# emojipad_v1.net
KiCad netlist of a schematic drawn in EAGLE
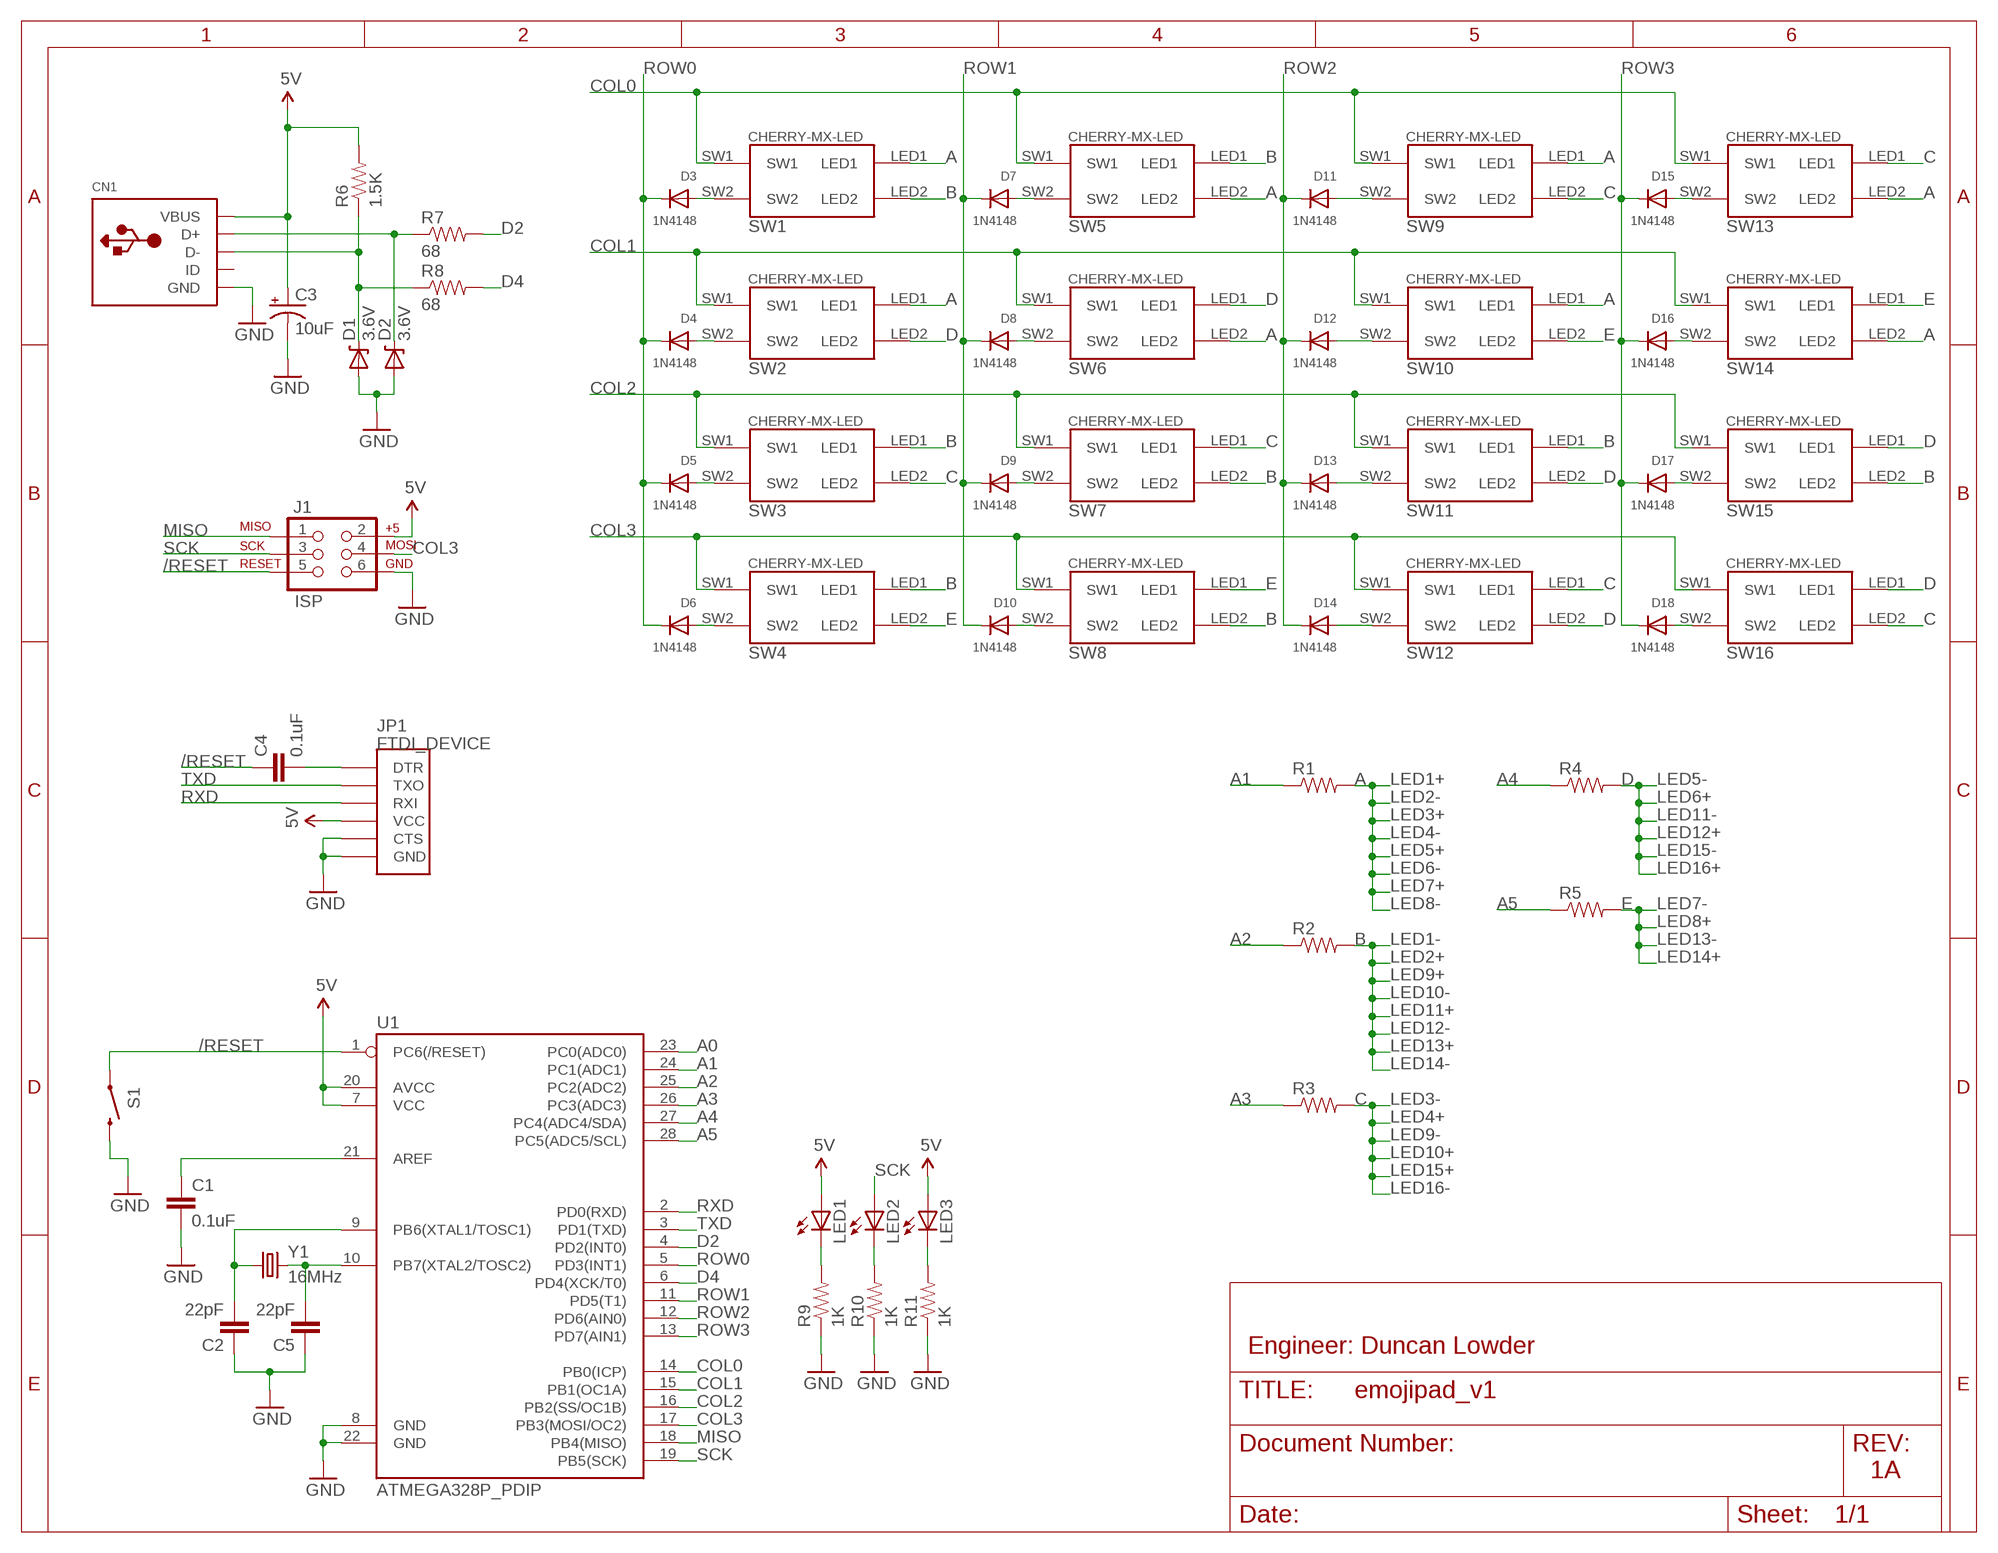
[diagram p0: schematic, sheet 1]

(export (version "E")
  (design (tool "Eeschema 10.0.6"))
  (components
    (comp (ref "C1")
      (value "0.1uF")
      (footprint "eagle-import:CAP-PTH-SMALL")
      (libsource (lib "eagle-import") (part "CAPPTH"))
    )
    (comp (ref "C2")
      (value "22pF")
      (footprint "eagle-import:CAP-PTH-SMALL")
      (libsource (lib "eagle-import") (part "CAPPTH"))
    )
    (comp (ref "C3")
      (value "10uF")
      (footprint "eagle-import:CPOL-RADIAL-10UF-25V")
      (libsource (lib "eagle-import") (part "CAP_POLPTH2"))
    )
    (comp (ref "C4")
      (value "0.1uF")
      (footprint "eagle-import:CAP-PTH-SMALL")
      (libsource (lib "eagle-import") (part "SparkFun-Passives_CAPPTH"))
    )
    (comp (ref "C5")
      (value "22pF")
      (footprint "eagle-import:CAP-PTH-SMALL")
      (libsource (lib "eagle-import") (part "CAPPTH"))
    )
    (comp (ref "CN1")
      (value "USBMOLEX")
      (footprint "eagle-import:USB-MINIB-THM-MOLEX")
      (libsource (lib "eagle-import") (part "USBMOLEX"))
    )
    (comp (ref "D1")
      (value "3.6V")
      (footprint "eagle-import:DIODE-ZENER")
      (libsource (lib "eagle-import") (part "DIODE-ZENERPTH"))
    )
    (comp (ref "D2")
      (value "3.6V")
      (footprint "eagle-import:DIODE-ZENER")
      (libsource (lib "eagle-import") (part "DIODE-ZENERPTH"))
    )
    (comp (ref "D3")
      (value "1N4148")
      (footprint "eagle-import:DO-1N4148")
      (libsource (lib "eagle-import") (part "DIODEDO-1N4148"))
    )
    (comp (ref "D4")
      (value "1N4148")
      (footprint "eagle-import:DO-1N4148")
      (libsource (lib "eagle-import") (part "DIODEDO-1N4148"))
    )
    (comp (ref "D5")
      (value "1N4148")
      (footprint "eagle-import:DO-1N4148")
      (libsource (lib "eagle-import") (part "DIODEDO-1N4148"))
    )
    (comp (ref "D6")
      (value "1N4148")
      (footprint "eagle-import:DO-1N4148")
      (libsource (lib "eagle-import") (part "DIODEDO-1N4148"))
    )
    (comp (ref "D7")
      (value "1N4148")
      (footprint "eagle-import:DO-1N4148")
      (libsource (lib "eagle-import") (part "DIODEDO-1N4148"))
    )
    (comp (ref "D8")
      (value "1N4148")
      (footprint "eagle-import:DO-1N4148")
      (libsource (lib "eagle-import") (part "DIODEDO-1N4148"))
    )
    (comp (ref "D9")
      (value "1N4148")
      (footprint "eagle-import:DO-1N4148")
      (libsource (lib "eagle-import") (part "DIODEDO-1N4148"))
    )
    (comp (ref "D10")
      (value "1N4148")
      (footprint "eagle-import:DO-1N4148")
      (libsource (lib "eagle-import") (part "DIODEDO-1N4148"))
    )
    (comp (ref "D11")
      (value "1N4148")
      (footprint "eagle-import:DO-1N4148")
      (libsource (lib "eagle-import") (part "DIODEDO-1N4148"))
    )
    (comp (ref "D12")
      (value "1N4148")
      (footprint "eagle-import:DO-1N4148")
      (libsource (lib "eagle-import") (part "DIODEDO-1N4148"))
    )
    (comp (ref "D13")
      (value "1N4148")
      (footprint "eagle-import:DO-1N4148")
      (libsource (lib "eagle-import") (part "DIODEDO-1N4148"))
    )
    (comp (ref "D14")
      (value "1N4148")
      (footprint "eagle-import:DO-1N4148")
      (libsource (lib "eagle-import") (part "DIODEDO-1N4148"))
    )
    (comp (ref "D15")
      (value "1N4148")
      (footprint "eagle-import:DO-1N4148")
      (libsource (lib "eagle-import") (part "DIODEDO-1N4148"))
    )
    (comp (ref "D16")
      (value "1N4148")
      (footprint "eagle-import:DO-1N4148")
      (libsource (lib "eagle-import") (part "DIODEDO-1N4148"))
    )
    (comp (ref "D17")
      (value "1N4148")
      (footprint "eagle-import:DO-1N4148")
      (libsource (lib "eagle-import") (part "DIODEDO-1N4148"))
    )
    (comp (ref "D18")
      (value "1N4148")
      (footprint "eagle-import:DO-1N4148")
      (libsource (lib "eagle-import") (part "DIODEDO-1N4148"))
    )
    (comp (ref "J1")
      (value "ISP")
      (footprint "eagle-import:2X3")
      (libsource (lib "eagle-import") (part "AVR_SPI_PRG_6PTH"))
    )
    (comp (ref "JP1")
      (value "FTDI_DEVICE")
      (footprint "eagle-import:FTDI_DEVICE_SIDE")
      (libsource (lib "eagle-import") (part "FTDI_DEVICE"))
    )
    (comp (ref "LED1")
      (value "LED3MM")
      (footprint "eagle-import:LED3MM")
      (libsource (lib "eagle-import") (part "LED3MM"))
    )
    (comp (ref "LED2")
      (value "LED3MM")
      (footprint "eagle-import:LED3MM")
      (libsource (lib "eagle-import") (part "LED3MM"))
    )
    (comp (ref "LED3")
      (value "LED3MM")
      (footprint "eagle-import:LED3MM")
      (libsource (lib "eagle-import") (part "LED3MM"))
    )
    (comp (ref "R1")
      (value "RESISTORAXIAL-0.3")
      (footprint "eagle-import:AXIAL-0.3")
      (libsource (lib "eagle-import") (part "RESISTORAXIAL-0.3"))
    )
    (comp (ref "R2")
      (value "RESISTORAXIAL-0.3")
      (footprint "eagle-import:AXIAL-0.3")
      (libsource (lib "eagle-import") (part "RESISTORAXIAL-0.3"))
    )
    (comp (ref "R3")
      (value "RESISTORAXIAL-0.3")
      (footprint "eagle-import:AXIAL-0.3")
      (libsource (lib "eagle-import") (part "RESISTORAXIAL-0.3"))
    )
    (comp (ref "R4")
      (value "RESISTORAXIAL-0.3")
      (footprint "eagle-import:AXIAL-0.3")
      (libsource (lib "eagle-import") (part "RESISTORAXIAL-0.3"))
    )
    (comp (ref "R5")
      (value "RESISTORAXIAL-0.3")
      (footprint "eagle-import:AXIAL-0.3")
      (libsource (lib "eagle-import") (part "RESISTORAXIAL-0.3"))
    )
    (comp (ref "R6")
      (value "1.5K")
      (footprint "eagle-import:AXIAL-0.3")
      (libsource (lib "eagle-import") (part "RESISTORAXIAL-0.3"))
    )
    (comp (ref "R7")
      (value "68")
      (footprint "eagle-import:AXIAL-0.3")
      (libsource (lib "eagle-import") (part "SparkFun-Resistors_RESISTORAXIAL-0.3"))
    )
    (comp (ref "R8")
      (value "68")
      (footprint "eagle-import:AXIAL-0.3")
      (libsource (lib "eagle-import") (part "SparkFun-Resistors_RESISTORAXIAL-0.3"))
    )
    (comp (ref "R9")
      (value "1K")
      (footprint "eagle-import:AXIAL-0.3")
      (libsource (lib "eagle-import") (part "RESISTORAXIAL-0.3"))
    )
    (comp (ref "R10")
      (value "1K")
      (footprint "eagle-import:AXIAL-0.3")
      (libsource (lib "eagle-import") (part "RESISTORAXIAL-0.3"))
    )
    (comp (ref "R11")
      (value "1K")
      (footprint "eagle-import:AXIAL-0.3")
      (libsource (lib "eagle-import") (part "RESISTORAXIAL-0.3"))
    )
    (comp (ref "S1")
      (value "SWITCH-MOMENTARY-2SIDE_EZ")
      (footprint "eagle-import:TACTILE-PTH-SIDEEZ")
      (libsource (lib "eagle-import") (part "SWITCH-MOMENTARY-2SIDE_EZ"))
    )
    (comp (ref "SW1")
      (value "CHERRY-MX-LED")
      (footprint "eagle-import:CHERRY-MX-LED")
      (libsource (lib "eagle-import") (part "CHERRY-MX-LED"))
    )
    (comp (ref "SW2")
      (value "CHERRY-MX-LED")
      (footprint "eagle-import:CHERRY-MX-LED")
      (libsource (lib "eagle-import") (part "CHERRY-MX-LED"))
    )
    (comp (ref "SW3")
      (value "CHERRY-MX-LED")
      (footprint "eagle-import:CHERRY-MX-LED")
      (libsource (lib "eagle-import") (part "CHERRY-MX-LED"))
    )
    (comp (ref "SW4")
      (value "CHERRY-MX-LED")
      (footprint "eagle-import:CHERRY-MX-LED")
      (libsource (lib "eagle-import") (part "CHERRY-MX-LED"))
    )
    (comp (ref "SW5")
      (value "CHERRY-MX-LED")
      (footprint "eagle-import:CHERRY-MX-LED")
      (libsource (lib "eagle-import") (part "CHERRY-MX-LED"))
    )
    (comp (ref "SW6")
      (value "CHERRY-MX-LED")
      (footprint "eagle-import:CHERRY-MX-LED")
      (libsource (lib "eagle-import") (part "CHERRY-MX-LED"))
    )
    (comp (ref "SW7")
      (value "CHERRY-MX-LED")
      (footprint "eagle-import:CHERRY-MX-LED")
      (libsource (lib "eagle-import") (part "CHERRY-MX-LED"))
    )
    (comp (ref "SW8")
      (value "CHERRY-MX-LED")
      (footprint "eagle-import:CHERRY-MX-LED")
      (libsource (lib "eagle-import") (part "CHERRY-MX-LED"))
    )
    (comp (ref "SW9")
      (value "CHERRY-MX-LED")
      (footprint "eagle-import:CHERRY-MX-LED")
      (libsource (lib "eagle-import") (part "CHERRY-MX-LED"))
    )
    (comp (ref "SW10")
      (value "CHERRY-MX-LED")
      (footprint "eagle-import:CHERRY-MX-LED")
      (libsource (lib "eagle-import") (part "CHERRY-MX-LED"))
    )
    (comp (ref "SW11")
      (value "CHERRY-MX-LED")
      (footprint "eagle-import:CHERRY-MX-LED")
      (libsource (lib "eagle-import") (part "CHERRY-MX-LED"))
    )
    (comp (ref "SW12")
      (value "CHERRY-MX-LED")
      (footprint "eagle-import:CHERRY-MX-LED")
      (libsource (lib "eagle-import") (part "CHERRY-MX-LED"))
    )
    (comp (ref "SW13")
      (value "CHERRY-MX-LED")
      (footprint "eagle-import:CHERRY-MX-LED")
      (libsource (lib "eagle-import") (part "CHERRY-MX-LED"))
    )
    (comp (ref "SW14")
      (value "CHERRY-MX-LED")
      (footprint "eagle-import:CHERRY-MX-LED")
      (libsource (lib "eagle-import") (part "CHERRY-MX-LED"))
    )
    (comp (ref "SW15")
      (value "CHERRY-MX-LED")
      (footprint "eagle-import:CHERRY-MX-LED")
      (libsource (lib "eagle-import") (part "CHERRY-MX-LED"))
    )
    (comp (ref "SW16")
      (value "CHERRY-MX-LED")
      (footprint "eagle-import:CHERRY-MX-LED")
      (libsource (lib "eagle-import") (part "CHERRY-MX-LED"))
    )
    (comp (ref "U1")
      (value "ATMEGA328P_PDIP")
      (footprint "eagle-import:DIL28-3")
      (libsource (lib "eagle-import") (part "ATMEGA328P_PDIP"))
    )
    (comp (ref "Y1")
      (value "16MHz")
      (footprint "eagle-import:HC49US")
      (libsource (lib "eagle-import") (part "CRYSTALHC49US"))
    )
  )
  (nets
    (net (code "1") (name "/A") (class "Default")
      (node (ref "R1") (pin "P$2") (pinfunction "2_P$2") (pintype "passive"))
      (node (ref "SW1") (pin "LED1") (pinfunction "LED1_LED1") (pintype "bidirectional"))
      (node (ref "SW10") (pin "LED1") (pinfunction "LED1_LED1") (pintype "bidirectional"))
      (node (ref "SW13") (pin "LED2") (pinfunction "LED2_LED2") (pintype "bidirectional"))
      (node (ref "SW14") (pin "LED2") (pinfunction "LED2_LED2") (pintype "bidirectional"))
      (node (ref "SW2") (pin "LED1") (pinfunction "LED1_LED1") (pintype "bidirectional"))
      (node (ref "SW5") (pin "LED2") (pinfunction "LED2_LED2") (pintype "bidirectional"))
      (node (ref "SW6") (pin "LED2") (pinfunction "LED2_LED2") (pintype "bidirectional"))
      (node (ref "SW9") (pin "LED1") (pinfunction "LED1_LED1") (pintype "bidirectional"))
    )
    (net (code "2") (name "/A0") (class "Default")
      (node (ref "U1") (pin "23") (pinfunction "PC0(ADC0)_23") (pintype "bidirectional"))
    )
    (net (code "3") (name "/A1") (class "Default")
      (node (ref "R1") (pin "P$1") (pinfunction "1_P$1") (pintype "passive"))
      (node (ref "U1") (pin "24") (pinfunction "PC1(ADC1)_24") (pintype "bidirectional"))
    )
    (net (code "4") (name "/A2") (class "Default")
      (node (ref "R2") (pin "P$1") (pinfunction "1_P$1") (pintype "passive"))
      (node (ref "U1") (pin "25") (pinfunction "PC2(ADC2)_25") (pintype "bidirectional"))
    )
    (net (code "5") (name "/A3") (class "Default")
      (node (ref "R3") (pin "P$1") (pinfunction "1_P$1") (pintype "passive"))
      (node (ref "U1") (pin "26") (pinfunction "PC3(ADC3)_26") (pintype "bidirectional"))
    )
    (net (code "6") (name "/A4") (class "Default")
      (node (ref "R4") (pin "P$1") (pinfunction "1_P$1") (pintype "passive"))
      (node (ref "U1") (pin "27") (pinfunction "PC4(ADC4/SDA)_27") (pintype "bidirectional"))
    )
    (net (code "7") (name "/A5") (class "Default")
      (node (ref "R5") (pin "P$1") (pinfunction "1_P$1") (pintype "passive"))
      (node (ref "U1") (pin "28") (pinfunction "PC5(ADC5/SCL)_28") (pintype "bidirectional"))
    )
    (net (code "8") (name "/B") (class "Default")
      (node (ref "R2") (pin "P$2") (pinfunction "2_P$2") (pintype "passive"))
      (node (ref "SW1") (pin "LED2") (pinfunction "LED2_LED2") (pintype "bidirectional"))
      (node (ref "SW11") (pin "LED1") (pinfunction "LED1_LED1") (pintype "bidirectional"))
      (node (ref "SW15") (pin "LED2") (pinfunction "LED2_LED2") (pintype "bidirectional"))
      (node (ref "SW3") (pin "LED1") (pinfunction "LED1_LED1") (pintype "bidirectional"))
      (node (ref "SW4") (pin "LED1") (pinfunction "LED1_LED1") (pintype "bidirectional"))
      (node (ref "SW5") (pin "LED1") (pinfunction "LED1_LED1") (pintype "bidirectional"))
      (node (ref "SW7") (pin "LED2") (pinfunction "LED2_LED2") (pintype "bidirectional"))
      (node (ref "SW8") (pin "LED2") (pinfunction "LED2_LED2") (pintype "bidirectional"))
    )
    (net (code "9") (name "/C") (class "Default")
      (node (ref "R3") (pin "P$2") (pinfunction "2_P$2") (pintype "passive"))
      (node (ref "SW12") (pin "LED1") (pinfunction "LED1_LED1") (pintype "bidirectional"))
      (node (ref "SW13") (pin "LED1") (pinfunction "LED1_LED1") (pintype "bidirectional"))
      (node (ref "SW16") (pin "LED2") (pinfunction "LED2_LED2") (pintype "bidirectional"))
      (node (ref "SW3") (pin "LED2") (pinfunction "LED2_LED2") (pintype "bidirectional"))
      (node (ref "SW7") (pin "LED1") (pinfunction "LED1_LED1") (pintype "bidirectional"))
      (node (ref "SW9") (pin "LED2") (pinfunction "LED2_LED2") (pintype "bidirectional"))
    )
    (net (code "10") (name "/COL0") (class "Default")
      (node (ref "SW1") (pin "SW1") (pinfunction "SW1_SW1") (pintype "bidirectional"))
      (node (ref "SW13") (pin "SW1") (pinfunction "SW1_SW1") (pintype "bidirectional"))
      (node (ref "SW5") (pin "SW1") (pinfunction "SW1_SW1") (pintype "bidirectional"))
      (node (ref "SW9") (pin "SW1") (pinfunction "SW1_SW1") (pintype "bidirectional"))
      (node (ref "U1") (pin "14") (pinfunction "PB0(ICP)_14") (pintype "bidirectional"))
    )
    (net (code "11") (name "/COL1") (class "Default")
      (node (ref "SW10") (pin "SW1") (pinfunction "SW1_SW1") (pintype "bidirectional"))
      (node (ref "SW14") (pin "SW1") (pinfunction "SW1_SW1") (pintype "bidirectional"))
      (node (ref "SW2") (pin "SW1") (pinfunction "SW1_SW1") (pintype "bidirectional"))
      (node (ref "SW6") (pin "SW1") (pinfunction "SW1_SW1") (pintype "bidirectional"))
      (node (ref "U1") (pin "15") (pinfunction "PB1(OC1A)_15") (pintype "bidirectional"))
    )
    (net (code "12") (name "/COL2") (class "Default")
      (node (ref "SW11") (pin "SW1") (pinfunction "SW1_SW1") (pintype "bidirectional"))
      (node (ref "SW15") (pin "SW1") (pinfunction "SW1_SW1") (pintype "bidirectional"))
      (node (ref "SW3") (pin "SW1") (pinfunction "SW1_SW1") (pintype "bidirectional"))
      (node (ref "SW7") (pin "SW1") (pinfunction "SW1_SW1") (pintype "bidirectional"))
      (node (ref "U1") (pin "16") (pinfunction "PB2(SS/OC1B)_16") (pintype "bidirectional"))
    )
    (net (code "13") (name "/COL3") (class "Default")
      (node (ref "J1") (pin "4") (pinfunction "4_4") (pintype "passive"))
      (node (ref "SW12") (pin "SW1") (pinfunction "SW1_SW1") (pintype "bidirectional"))
      (node (ref "SW16") (pin "SW1") (pinfunction "SW1_SW1") (pintype "bidirectional"))
      (node (ref "SW4") (pin "SW1") (pinfunction "SW1_SW1") (pintype "bidirectional"))
      (node (ref "SW8") (pin "SW1") (pinfunction "SW1_SW1") (pintype "bidirectional"))
      (node (ref "U1") (pin "17") (pinfunction "PB3(MOSI/OC2)_17") (pintype "bidirectional"))
    )
    (net (code "14") (name "/D") (class "Default")
      (node (ref "R4") (pin "P$2") (pinfunction "2_P$2") (pintype "passive"))
      (node (ref "SW11") (pin "LED2") (pinfunction "LED2_LED2") (pintype "bidirectional"))
      (node (ref "SW12") (pin "LED2") (pinfunction "LED2_LED2") (pintype "bidirectional"))
      (node (ref "SW15") (pin "LED1") (pinfunction "LED1_LED1") (pintype "bidirectional"))
      (node (ref "SW16") (pin "LED1") (pinfunction "LED1_LED1") (pintype "bidirectional"))
      (node (ref "SW2") (pin "LED2") (pinfunction "LED2_LED2") (pintype "bidirectional"))
      (node (ref "SW6") (pin "LED1") (pinfunction "LED1_LED1") (pintype "bidirectional"))
    )
    (net (code "15") (name "/D2") (class "Default")
      (node (ref "R7") (pin "P$2") (pinfunction "2_P$2") (pintype "passive"))
      (node (ref "U1") (pin "4") (pinfunction "PD2(INT0)_4") (pintype "bidirectional"))
    )
    (net (code "16") (name "/D4") (class "Default")
      (node (ref "R8") (pin "P$2") (pinfunction "2_P$2") (pintype "passive"))
      (node (ref "U1") (pin "6") (pinfunction "PD4(XCK/T0)_6") (pintype "bidirectional"))
    )
    (net (code "17") (name "/E") (class "Default")
      (node (ref "R5") (pin "P$2") (pinfunction "2_P$2") (pintype "passive"))
      (node (ref "SW10") (pin "LED2") (pinfunction "LED2_LED2") (pintype "bidirectional"))
      (node (ref "SW14") (pin "LED1") (pinfunction "LED1_LED1") (pintype "bidirectional"))
      (node (ref "SW4") (pin "LED2") (pinfunction "LED2_LED2") (pintype "bidirectional"))
      (node (ref "SW8") (pin "LED1") (pinfunction "LED1_LED1") (pintype "bidirectional"))
    )
    (net (code "18") (name "/MISO") (class "Default")
      (node (ref "J1") (pin "1") (pinfunction "1_1") (pintype "passive"))
      (node (ref "U1") (pin "18") (pinfunction "PB4(MISO)_18") (pintype "bidirectional"))
    )
    (net (code "19") (name "/ROW0") (class "Default")
      (node (ref "D3") (pin "C") (pinfunction "C_C") (pintype "passive"))
      (node (ref "D4") (pin "C") (pinfunction "C_C") (pintype "passive"))
      (node (ref "D5") (pin "C") (pinfunction "C_C") (pintype "passive"))
      (node (ref "D6") (pin "C") (pinfunction "C_C") (pintype "passive"))
      (node (ref "U1") (pin "5") (pinfunction "PD3(INT1)_5") (pintype "bidirectional"))
    )
    (net (code "20") (name "/ROW1") (class "Default")
      (node (ref "D10") (pin "C") (pinfunction "C_C") (pintype "passive"))
      (node (ref "D7") (pin "C") (pinfunction "C_C") (pintype "passive"))
      (node (ref "D8") (pin "C") (pinfunction "C_C") (pintype "passive"))
      (node (ref "D9") (pin "C") (pinfunction "C_C") (pintype "passive"))
      (node (ref "U1") (pin "11") (pinfunction "PD5(T1)_11") (pintype "bidirectional"))
    )
    (net (code "21") (name "/ROW2") (class "Default")
      (node (ref "D11") (pin "C") (pinfunction "C_C") (pintype "passive"))
      (node (ref "D12") (pin "C") (pinfunction "C_C") (pintype "passive"))
      (node (ref "D13") (pin "C") (pinfunction "C_C") (pintype "passive"))
      (node (ref "D14") (pin "C") (pinfunction "C_C") (pintype "passive"))
      (node (ref "U1") (pin "12") (pinfunction "PD6(AIN0)_12") (pintype "bidirectional"))
    )
    (net (code "22") (name "/ROW3") (class "Default")
      (node (ref "D15") (pin "C") (pinfunction "C_C") (pintype "passive"))
      (node (ref "D16") (pin "C") (pinfunction "C_C") (pintype "passive"))
      (node (ref "D17") (pin "C") (pinfunction "C_C") (pintype "passive"))
      (node (ref "D18") (pin "C") (pinfunction "C_C") (pintype "passive"))
      (node (ref "U1") (pin "13") (pinfunction "PD7(AIN1)_13") (pintype "bidirectional"))
    )
    (net (code "23") (name "/RXD") (class "Default")
      (node (ref "JP1") (pin "P$3") (pinfunction "RXI_P$3") (pintype "bidirectional"))
      (node (ref "U1") (pin "2") (pinfunction "PD0(RXD)_2") (pintype "bidirectional"))
    )
    (net (code "24") (name "/SCK") (class "Default")
      (node (ref "J1") (pin "3") (pinfunction "3_3") (pintype "passive"))
      (node (ref "LED2") (pin "A") (pinfunction "A_A") (pintype "passive"))
      (node (ref "U1") (pin "19") (pinfunction "PB5(SCK)_19") (pintype "bidirectional"))
    )
    (net (code "25") (name "/TXD") (class "Default")
      (node (ref "JP1") (pin "P$2") (pinfunction "TXO_P$2") (pintype "bidirectional"))
      (node (ref "U1") (pin "3") (pinfunction "PD1(TXD)_3") (pintype "bidirectional"))
    )
    (net (code "26") (name "/{slash}RESET") (class "Default")
      (node (ref "C4") (pin "1") (pinfunction "1_1") (pintype "passive"))
      (node (ref "J1") (pin "5") (pinfunction "5_5") (pintype "passive"))
      (node (ref "S1") (pin "1") (pinfunction "1_1") (pintype "passive"))
      (node (ref "U1") (pin "1") (pinfunction "PC6(/RESET)_1") (pintype "bidirectional"))
    )
    (net (code "27") (name "5V") (class "Default")
      (node (ref "C3") (pin "1") (pinfunction "+_1") (pintype "passive"))
      (node (ref "CN1") (pin "VBUS") (pinfunction "VBUS_VBUS") (pintype "power_in"))
      (node (ref "J1") (pin "2") (pinfunction "2_2") (pintype "passive"))
      (node (ref "JP1") (pin "P$4") (pinfunction "VCC_P$4") (pintype "bidirectional"))
      (node (ref "LED1") (pin "A") (pinfunction "A_A") (pintype "passive"))
      (node (ref "LED3") (pin "A") (pinfunction "A_A") (pintype "passive"))
      (node (ref "R6") (pin "P$2") (pinfunction "2_P$2") (pintype "passive"))
      (node (ref "U1") (pin "20") (pinfunction "AVCC_20") (pintype "bidirectional"))
      (node (ref "U1") (pin "7") (pinfunction "VCC_7") (pintype "bidirectional"))
    )
    (net (code "28") (name "GND") (class "Default")
      (node (ref "C1") (pin "2") (pinfunction "2_2") (pintype "passive"))
      (node (ref "C2") (pin "1") (pinfunction "1_1") (pintype "passive"))
      (node (ref "C3") (pin "2") (pinfunction "-_2") (pintype "passive"))
      (node (ref "C5") (pin "1") (pinfunction "1_1") (pintype "passive"))
      (node (ref "CN1") (pin "GND") (pinfunction "GND_GND") (pintype "power_in"))
      (node (ref "D1") (pin "P$2") (pinfunction "A_P$2") (pintype "passive"))
      (node (ref "D2") (pin "P$2") (pinfunction "A_P$2") (pintype "passive"))
      (node (ref "J1") (pin "6") (pinfunction "6_6") (pintype "passive"))
      (node (ref "JP1") (pin "P$5") (pinfunction "CTS_P$5") (pintype "bidirectional"))
      (node (ref "JP1") (pin "P$6") (pinfunction "GND_P$6") (pintype "bidirectional"))
      (node (ref "R10") (pin "P$1") (pinfunction "1_P$1") (pintype "passive"))
      (node (ref "R11") (pin "P$1") (pinfunction "1_P$1") (pintype "passive"))
      (node (ref "R9") (pin "P$1") (pinfunction "1_P$1") (pintype "passive"))
      (node (ref "S1") (pin "2") (pinfunction "2_2") (pintype "passive"))
      (node (ref "U1") (pin "22") (pinfunction "GND_22") (pintype "bidirectional"))
      (node (ref "U1") (pin "8") (pinfunction "GND_8") (pintype "bidirectional"))
    )
    (net (code "29") (name "Net-(D1-C)") (class "Default")
      (node (ref "CN1") (pin "D-") (pinfunction "D-_D-") (pintype "bidirectional"))
      (node (ref "D1") (pin "P$1") (pinfunction "C_P$1") (pintype "passive"))
      (node (ref "R6") (pin "P$1") (pinfunction "1_P$1") (pintype "passive"))
      (node (ref "R8") (pin "P$1") (pinfunction "1_P$1") (pintype "passive"))
    )
    (net (code "30") (name "Net-(D2-C)") (class "Default")
      (node (ref "CN1") (pin "D+") (pinfunction "D+_D+") (pintype "bidirectional"))
      (node (ref "D2") (pin "P$1") (pinfunction "C_P$1") (pintype "passive"))
      (node (ref "R7") (pin "P$1") (pinfunction "1_P$1") (pintype "passive"))
    )
    (net (code "31") (name "Net-(D3-PadA)") (class "Default")
      (node (ref "D3") (pin "A") (pinfunction "A_A") (pintype "passive"))
      (node (ref "SW1") (pin "SW2") (pinfunction "SW2_SW2") (pintype "bidirectional"))
    )
    (net (code "32") (name "Net-(D4-PadA)") (class "Default")
      (node (ref "D4") (pin "A") (pinfunction "A_A") (pintype "passive"))
      (node (ref "SW2") (pin "SW2") (pinfunction "SW2_SW2") (pintype "bidirectional"))
    )
    (net (code "33") (name "Net-(D5-PadA)") (class "Default")
      (node (ref "D5") (pin "A") (pinfunction "A_A") (pintype "passive"))
      (node (ref "SW3") (pin "SW2") (pinfunction "SW2_SW2") (pintype "bidirectional"))
    )
    (net (code "34") (name "Net-(D6-PadA)") (class "Default")
      (node (ref "D6") (pin "A") (pinfunction "A_A") (pintype "passive"))
      (node (ref "SW4") (pin "SW2") (pinfunction "SW2_SW2") (pintype "bidirectional"))
    )
    (net (code "35") (name "Net-(D7-PadA)") (class "Default")
      (node (ref "D7") (pin "A") (pinfunction "A_A") (pintype "passive"))
      (node (ref "SW5") (pin "SW2") (pinfunction "SW2_SW2") (pintype "bidirectional"))
    )
    (net (code "36") (name "Net-(D8-PadA)") (class "Default")
      (node (ref "D8") (pin "A") (pinfunction "A_A") (pintype "passive"))
      (node (ref "SW6") (pin "SW2") (pinfunction "SW2_SW2") (pintype "bidirectional"))
    )
    (net (code "37") (name "Net-(D9-PadA)") (class "Default")
      (node (ref "D9") (pin "A") (pinfunction "A_A") (pintype "passive"))
      (node (ref "SW7") (pin "SW2") (pinfunction "SW2_SW2") (pintype "bidirectional"))
    )
    (net (code "38") (name "Net-(D10-PadA)") (class "Default")
      (node (ref "D10") (pin "A") (pinfunction "A_A") (pintype "passive"))
      (node (ref "SW8") (pin "SW2") (pinfunction "SW2_SW2") (pintype "bidirectional"))
    )
    (net (code "39") (name "Net-(D11-PadA)") (class "Default")
      (node (ref "D11") (pin "A") (pinfunction "A_A") (pintype "passive"))
      (node (ref "SW9") (pin "SW2") (pinfunction "SW2_SW2") (pintype "bidirectional"))
    )
    (net (code "40") (name "Net-(D12-PadA)") (class "Default")
      (node (ref "D12") (pin "A") (pinfunction "A_A") (pintype "passive"))
      (node (ref "SW10") (pin "SW2") (pinfunction "SW2_SW2") (pintype "bidirectional"))
    )
    (net (code "41") (name "Net-(D13-PadA)") (class "Default")
      (node (ref "D13") (pin "A") (pinfunction "A_A") (pintype "passive"))
      (node (ref "SW11") (pin "SW2") (pinfunction "SW2_SW2") (pintype "bidirectional"))
    )
    (net (code "42") (name "Net-(D14-PadA)") (class "Default")
      (node (ref "D14") (pin "A") (pinfunction "A_A") (pintype "passive"))
      (node (ref "SW12") (pin "SW2") (pinfunction "SW2_SW2") (pintype "bidirectional"))
    )
    (net (code "43") (name "Net-(D15-PadA)") (class "Default")
      (node (ref "D15") (pin "A") (pinfunction "A_A") (pintype "passive"))
      (node (ref "SW13") (pin "SW2") (pinfunction "SW2_SW2") (pintype "bidirectional"))
    )
    (net (code "44") (name "Net-(D16-PadA)") (class "Default")
      (node (ref "D16") (pin "A") (pinfunction "A_A") (pintype "passive"))
      (node (ref "SW14") (pin "SW2") (pinfunction "SW2_SW2") (pintype "bidirectional"))
    )
    (net (code "45") (name "Net-(D17-PadA)") (class "Default")
      (node (ref "D17") (pin "A") (pinfunction "A_A") (pintype "passive"))
      (node (ref "SW15") (pin "SW2") (pinfunction "SW2_SW2") (pintype "bidirectional"))
    )
    (net (code "46") (name "Net-(D18-PadA)") (class "Default")
      (node (ref "D18") (pin "A") (pinfunction "A_A") (pintype "passive"))
      (node (ref "SW16") (pin "SW2") (pinfunction "SW2_SW2") (pintype "bidirectional"))
    )
    (net (code "47") (name "Net-(JP1-DTR)") (class "Default")
      (node (ref "C4") (pin "2") (pinfunction "2_2") (pintype "passive"))
      (node (ref "JP1") (pin "P$1") (pinfunction "DTR_P$1") (pintype "bidirectional"))
    )
    (net (code "48") (name "Net-(LED1-C)") (class "Default")
      (node (ref "LED1") (pin "K") (pinfunction "C_K") (pintype "passive"))
      (node (ref "R9") (pin "P$2") (pinfunction "2_P$2") (pintype "passive"))
    )
    (net (code "49") (name "Net-(LED2-C)") (class "Default")
      (node (ref "LED2") (pin "K") (pinfunction "C_K") (pintype "passive"))
      (node (ref "R10") (pin "P$2") (pinfunction "2_P$2") (pintype "passive"))
    )
    (net (code "50") (name "Net-(LED3-C)") (class "Default")
      (node (ref "LED3") (pin "K") (pinfunction "C_K") (pintype "passive"))
      (node (ref "R11") (pin "P$2") (pinfunction "2_P$2") (pintype "passive"))
    )
    (net (code "51") (name "Net-(U1-AREF)") (class "Default")
      (node (ref "C1") (pin "1") (pinfunction "1_1") (pintype "passive"))
      (node (ref "U1") (pin "21") (pinfunction "AREF_21") (pintype "bidirectional"))
    )
    (net (code "52") (name "Net-(U1-PB6(XTAL1{slash}TOSC1))") (class "Default")
      (node (ref "C2") (pin "2") (pinfunction "2_2") (pintype "passive"))
      (node (ref "U1") (pin "9") (pinfunction "PB6(XTAL1/TOSC1)_9") (pintype "bidirectional"))
      (node (ref "Y1") (pin "1") (pinfunction "1_1") (pintype "passive"))
    )
    (net (code "53") (name "Net-(U1-PB7(XTAL2{slash}TOSC2))") (class "Default")
      (node (ref "C5") (pin "2") (pinfunction "2_2") (pintype "passive"))
      (node (ref "U1") (pin "10") (pinfunction "PB7(XTAL2/TOSC2)_10") (pintype "bidirectional"))
      (node (ref "Y1") (pin "2") (pinfunction "2_2") (pintype "passive"))
    )
    (net (code "54") (name "unconnected-(CN1-PadID)") (class "Default")
      (node (ref "CN1") (pin "ID") (pinfunction "ID_ID") (pintype "bidirectional"))
    )
  )
)
